# smallTransBrd.net
KiCad netlist of a schematic drawn in EAGLE
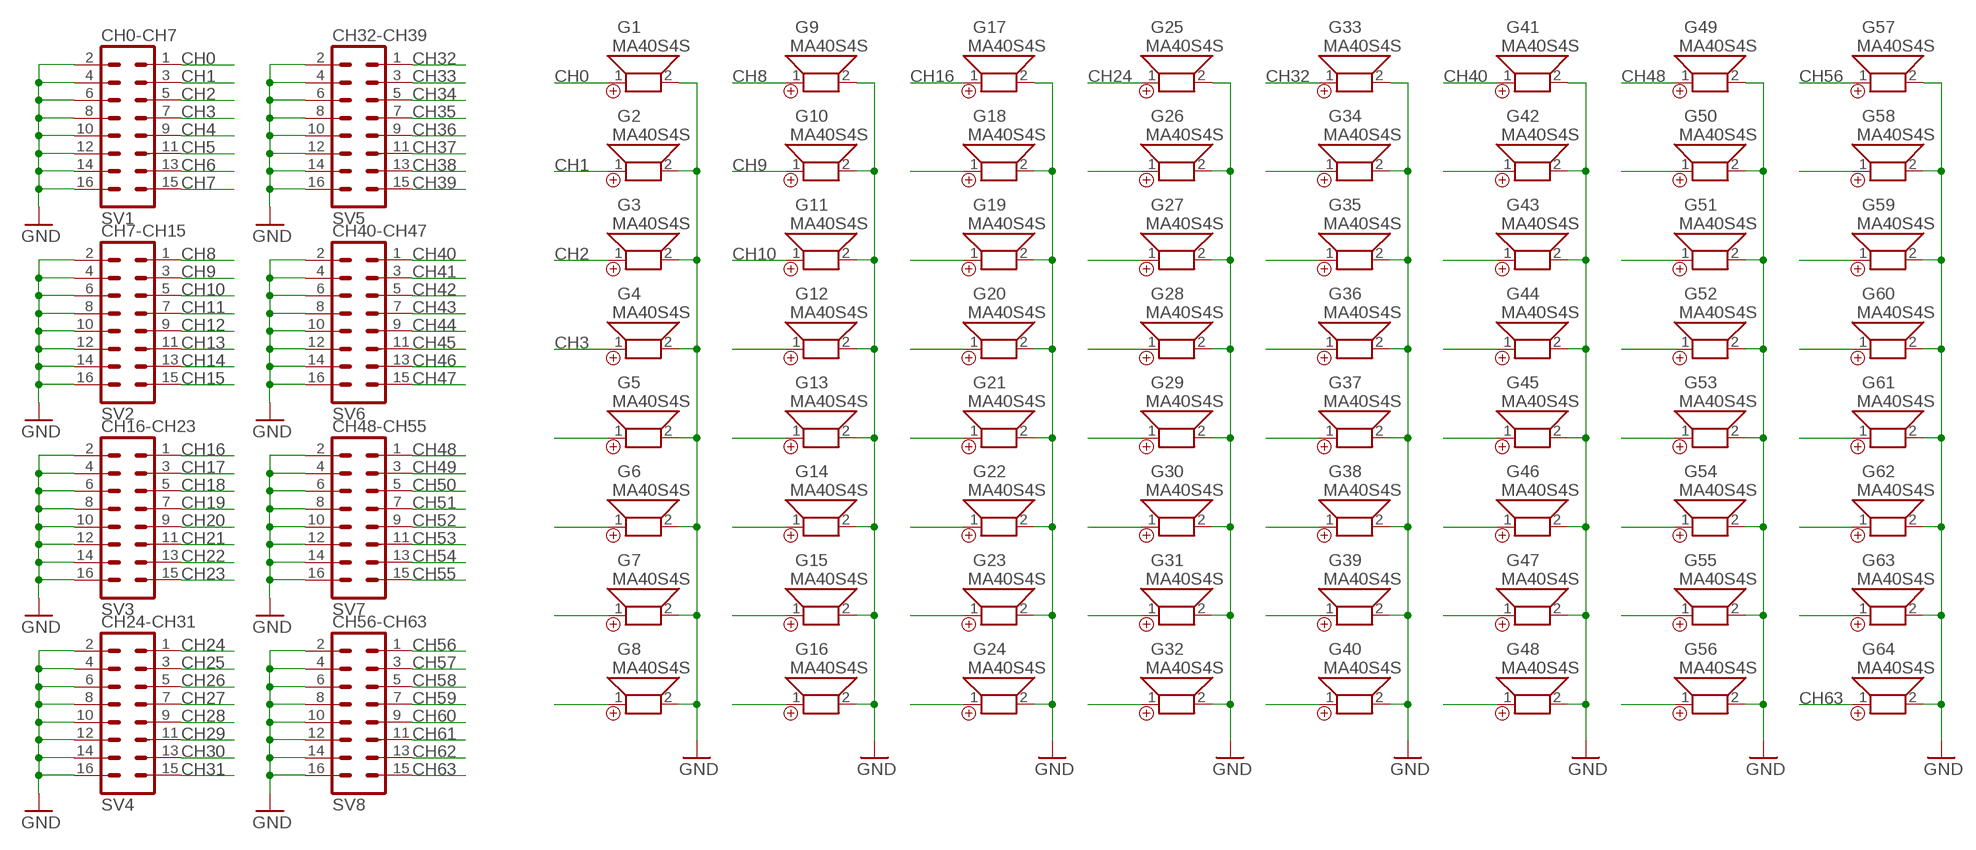
[diagram p0: schematic, sheet 1]

(export (version "E")
  (design (tool "Eeschema 10.0.6"))
  (components
    (comp (ref "G1")
      (value "MA40S4S")
      (footprint "eagle-import:MA40S4S")
      (libsource (lib "eagle-import") (part "MA40S4S"))
    )
    (comp (ref "G2")
      (value "MA40S4S")
      (footprint "eagle-import:MA40S4S")
      (libsource (lib "eagle-import") (part "MA40S4S"))
    )
    (comp (ref "G3")
      (value "MA40S4S")
      (footprint "eagle-import:MA40S4S")
      (libsource (lib "eagle-import") (part "MA40S4S"))
    )
    (comp (ref "G4")
      (value "MA40S4S")
      (footprint "eagle-import:MA40S4S")
      (libsource (lib "eagle-import") (part "MA40S4S"))
    )
    (comp (ref "G5")
      (value "MA40S4S")
      (footprint "eagle-import:MA40S4S")
      (libsource (lib "eagle-import") (part "MA40S4S"))
    )
    (comp (ref "G6")
      (value "MA40S4S")
      (footprint "eagle-import:MA40S4S")
      (libsource (lib "eagle-import") (part "MA40S4S"))
    )
    (comp (ref "G7")
      (value "MA40S4S")
      (footprint "eagle-import:MA40S4S")
      (libsource (lib "eagle-import") (part "MA40S4S"))
    )
    (comp (ref "G8")
      (value "MA40S4S")
      (footprint "eagle-import:MA40S4S")
      (libsource (lib "eagle-import") (part "MA40S4S"))
    )
    (comp (ref "G9")
      (value "MA40S4S")
      (footprint "eagle-import:MA40S4S")
      (libsource (lib "eagle-import") (part "MA40S4S"))
    )
    (comp (ref "G10")
      (value "MA40S4S")
      (footprint "eagle-import:MA40S4S")
      (libsource (lib "eagle-import") (part "MA40S4S"))
    )
    (comp (ref "G11")
      (value "MA40S4S")
      (footprint "eagle-import:MA40S4S")
      (libsource (lib "eagle-import") (part "MA40S4S"))
    )
    (comp (ref "G12")
      (value "MA40S4S")
      (footprint "eagle-import:MA40S4S")
      (libsource (lib "eagle-import") (part "MA40S4S"))
    )
    (comp (ref "G13")
      (value "MA40S4S")
      (footprint "eagle-import:MA40S4S")
      (libsource (lib "eagle-import") (part "MA40S4S"))
    )
    (comp (ref "G14")
      (value "MA40S4S")
      (footprint "eagle-import:MA40S4S")
      (libsource (lib "eagle-import") (part "MA40S4S"))
    )
    (comp (ref "G15")
      (value "MA40S4S")
      (footprint "eagle-import:MA40S4S")
      (libsource (lib "eagle-import") (part "MA40S4S"))
    )
    (comp (ref "G16")
      (value "MA40S4S")
      (footprint "eagle-import:MA40S4S")
      (libsource (lib "eagle-import") (part "MA40S4S"))
    )
    (comp (ref "G17")
      (value "MA40S4S")
      (footprint "eagle-import:MA40S4S")
      (libsource (lib "eagle-import") (part "MA40S4S"))
    )
    (comp (ref "G18")
      (value "MA40S4S")
      (footprint "eagle-import:MA40S4S")
      (libsource (lib "eagle-import") (part "MA40S4S"))
    )
    (comp (ref "G19")
      (value "MA40S4S")
      (footprint "eagle-import:MA40S4S")
      (libsource (lib "eagle-import") (part "MA40S4S"))
    )
    (comp (ref "G20")
      (value "MA40S4S")
      (footprint "eagle-import:MA40S4S")
      (libsource (lib "eagle-import") (part "MA40S4S"))
    )
    (comp (ref "G21")
      (value "MA40S4S")
      (footprint "eagle-import:MA40S4S")
      (libsource (lib "eagle-import") (part "MA40S4S"))
    )
    (comp (ref "G22")
      (value "MA40S4S")
      (footprint "eagle-import:MA40S4S")
      (libsource (lib "eagle-import") (part "MA40S4S"))
    )
    (comp (ref "G23")
      (value "MA40S4S")
      (footprint "eagle-import:MA40S4S")
      (libsource (lib "eagle-import") (part "MA40S4S"))
    )
    (comp (ref "G24")
      (value "MA40S4S")
      (footprint "eagle-import:MA40S4S")
      (libsource (lib "eagle-import") (part "MA40S4S"))
    )
    (comp (ref "G25")
      (value "MA40S4S")
      (footprint "eagle-import:MA40S4S")
      (libsource (lib "eagle-import") (part "MA40S4S"))
    )
    (comp (ref "G26")
      (value "MA40S4S")
      (footprint "eagle-import:MA40S4S")
      (libsource (lib "eagle-import") (part "MA40S4S"))
    )
    (comp (ref "G27")
      (value "MA40S4S")
      (footprint "eagle-import:MA40S4S")
      (libsource (lib "eagle-import") (part "MA40S4S"))
    )
    (comp (ref "G28")
      (value "MA40S4S")
      (footprint "eagle-import:MA40S4S")
      (libsource (lib "eagle-import") (part "MA40S4S"))
    )
    (comp (ref "G29")
      (value "MA40S4S")
      (footprint "eagle-import:MA40S4S")
      (libsource (lib "eagle-import") (part "MA40S4S"))
    )
    (comp (ref "G30")
      (value "MA40S4S")
      (footprint "eagle-import:MA40S4S")
      (libsource (lib "eagle-import") (part "MA40S4S"))
    )
    (comp (ref "G31")
      (value "MA40S4S")
      (footprint "eagle-import:MA40S4S")
      (libsource (lib "eagle-import") (part "MA40S4S"))
    )
    (comp (ref "G32")
      (value "MA40S4S")
      (footprint "eagle-import:MA40S4S")
      (libsource (lib "eagle-import") (part "MA40S4S"))
    )
    (comp (ref "G33")
      (value "MA40S4S")
      (footprint "eagle-import:MA40S4S")
      (libsource (lib "eagle-import") (part "MA40S4S"))
    )
    (comp (ref "G34")
      (value "MA40S4S")
      (footprint "eagle-import:MA40S4S")
      (libsource (lib "eagle-import") (part "MA40S4S"))
    )
    (comp (ref "G35")
      (value "MA40S4S")
      (footprint "eagle-import:MA40S4S")
      (libsource (lib "eagle-import") (part "MA40S4S"))
    )
    (comp (ref "G36")
      (value "MA40S4S")
      (footprint "eagle-import:MA40S4S")
      (libsource (lib "eagle-import") (part "MA40S4S"))
    )
    (comp (ref "G37")
      (value "MA40S4S")
      (footprint "eagle-import:MA40S4S")
      (libsource (lib "eagle-import") (part "MA40S4S"))
    )
    (comp (ref "G38")
      (value "MA40S4S")
      (footprint "eagle-import:MA40S4S")
      (libsource (lib "eagle-import") (part "MA40S4S"))
    )
    (comp (ref "G39")
      (value "MA40S4S")
      (footprint "eagle-import:MA40S4S")
      (libsource (lib "eagle-import") (part "MA40S4S"))
    )
    (comp (ref "G40")
      (value "MA40S4S")
      (footprint "eagle-import:MA40S4S")
      (libsource (lib "eagle-import") (part "MA40S4S"))
    )
    (comp (ref "G41")
      (value "MA40S4S")
      (footprint "eagle-import:MA40S4S")
      (libsource (lib "eagle-import") (part "MA40S4S"))
    )
    (comp (ref "G42")
      (value "MA40S4S")
      (footprint "eagle-import:MA40S4S")
      (libsource (lib "eagle-import") (part "MA40S4S"))
    )
    (comp (ref "G43")
      (value "MA40S4S")
      (footprint "eagle-import:MA40S4S")
      (libsource (lib "eagle-import") (part "MA40S4S"))
    )
    (comp (ref "G44")
      (value "MA40S4S")
      (footprint "eagle-import:MA40S4S")
      (libsource (lib "eagle-import") (part "MA40S4S"))
    )
    (comp (ref "G45")
      (value "MA40S4S")
      (footprint "eagle-import:MA40S4S")
      (libsource (lib "eagle-import") (part "MA40S4S"))
    )
    (comp (ref "G46")
      (value "MA40S4S")
      (footprint "eagle-import:MA40S4S")
      (libsource (lib "eagle-import") (part "MA40S4S"))
    )
    (comp (ref "G47")
      (value "MA40S4S")
      (footprint "eagle-import:MA40S4S")
      (libsource (lib "eagle-import") (part "MA40S4S"))
    )
    (comp (ref "G48")
      (value "MA40S4S")
      (footprint "eagle-import:MA40S4S")
      (libsource (lib "eagle-import") (part "MA40S4S"))
    )
    (comp (ref "G49")
      (value "MA40S4S")
      (footprint "eagle-import:MA40S4S")
      (libsource (lib "eagle-import") (part "MA40S4S"))
    )
    (comp (ref "G50")
      (value "MA40S4S")
      (footprint "eagle-import:MA40S4S")
      (libsource (lib "eagle-import") (part "MA40S4S"))
    )
    (comp (ref "G51")
      (value "MA40S4S")
      (footprint "eagle-import:MA40S4S")
      (libsource (lib "eagle-import") (part "MA40S4S"))
    )
    (comp (ref "G52")
      (value "MA40S4S")
      (footprint "eagle-import:MA40S4S")
      (libsource (lib "eagle-import") (part "MA40S4S"))
    )
    (comp (ref "G53")
      (value "MA40S4S")
      (footprint "eagle-import:MA40S4S")
      (libsource (lib "eagle-import") (part "MA40S4S"))
    )
    (comp (ref "G54")
      (value "MA40S4S")
      (footprint "eagle-import:MA40S4S")
      (libsource (lib "eagle-import") (part "MA40S4S"))
    )
    (comp (ref "G55")
      (value "MA40S4S")
      (footprint "eagle-import:MA40S4S")
      (libsource (lib "eagle-import") (part "MA40S4S"))
    )
    (comp (ref "G56")
      (value "MA40S4S")
      (footprint "eagle-import:MA40S4S")
      (libsource (lib "eagle-import") (part "MA40S4S"))
    )
    (comp (ref "G57")
      (value "MA40S4S")
      (footprint "eagle-import:MA40S4S")
      (libsource (lib "eagle-import") (part "MA40S4S"))
    )
    (comp (ref "G58")
      (value "MA40S4S")
      (footprint "eagle-import:MA40S4S")
      (libsource (lib "eagle-import") (part "MA40S4S"))
    )
    (comp (ref "G59")
      (value "MA40S4S")
      (footprint "eagle-import:MA40S4S")
      (libsource (lib "eagle-import") (part "MA40S4S"))
    )
    (comp (ref "G60")
      (value "MA40S4S")
      (footprint "eagle-import:MA40S4S")
      (libsource (lib "eagle-import") (part "MA40S4S"))
    )
    (comp (ref "G61")
      (value "MA40S4S")
      (footprint "eagle-import:MA40S4S")
      (libsource (lib "eagle-import") (part "MA40S4S"))
    )
    (comp (ref "G62")
      (value "MA40S4S")
      (footprint "eagle-import:MA40S4S")
      (libsource (lib "eagle-import") (part "MA40S4S"))
    )
    (comp (ref "G63")
      (value "MA40S4S")
      (footprint "eagle-import:MA40S4S")
      (libsource (lib "eagle-import") (part "MA40S4S"))
    )
    (comp (ref "G64")
      (value "MA40S4S")
      (footprint "eagle-import:MA40S4S")
      (libsource (lib "eagle-import") (part "MA40S4S"))
    )
    (comp (ref "SV1")
      (value "CH0-CH7")
      (footprint "eagle-import:ML16")
      (libsource (lib "eagle-import") (part "ML16"))
    )
    (comp (ref "SV2")
      (value "CH7-CH15")
      (footprint "eagle-import:ML16")
      (libsource (lib "eagle-import") (part "ML16"))
    )
    (comp (ref "SV3")
      (value "CH16-CH23")
      (footprint "eagle-import:ML16")
      (libsource (lib "eagle-import") (part "ML16"))
    )
    (comp (ref "SV4")
      (value "CH24-CH31")
      (footprint "eagle-import:ML16")
      (libsource (lib "eagle-import") (part "ML16"))
    )
    (comp (ref "SV5")
      (value "CH32-CH39")
      (footprint "eagle-import:ML16")
      (libsource (lib "eagle-import") (part "ML16"))
    )
    (comp (ref "SV6")
      (value "CH40-CH47")
      (footprint "eagle-import:ML16")
      (libsource (lib "eagle-import") (part "ML16"))
    )
    (comp (ref "SV7")
      (value "CH48-CH55")
      (footprint "eagle-import:ML16")
      (libsource (lib "eagle-import") (part "ML16"))
    )
    (comp (ref "SV8")
      (value "CH56-CH63")
      (footprint "eagle-import:ML16")
      (libsource (lib "eagle-import") (part "ML16"))
    )
  )
  (nets
    (net (code "1") (name "/CH0") (class "Default")
      (node (ref "G1") (pin "1") (pinfunction "1_1") (pintype "passive"))
      (node (ref "SV1") (pin "1") (pinfunction "1_1") (pintype "passive"))
    )
    (net (code "2") (name "/CH1") (class "Default")
      (node (ref "G2") (pin "1") (pinfunction "1_1") (pintype "passive"))
      (node (ref "SV1") (pin "3") (pinfunction "3_3") (pintype "passive"))
    )
    (net (code "3") (name "/CH2") (class "Default")
      (node (ref "G3") (pin "1") (pinfunction "1_1") (pintype "passive"))
      (node (ref "SV1") (pin "5") (pinfunction "5_5") (pintype "passive"))
    )
    (net (code "4") (name "/CH3") (class "Default")
      (node (ref "G4") (pin "1") (pinfunction "1_1") (pintype "passive"))
      (node (ref "SV1") (pin "7") (pinfunction "7_7") (pintype "passive"))
    )
    (net (code "5") (name "/CH4") (class "Default")
      (node (ref "G5") (pin "1") (pinfunction "1_1") (pintype "passive"))
      (node (ref "SV1") (pin "9") (pinfunction "9_9") (pintype "passive"))
    )
    (net (code "6") (name "/CH5") (class "Default")
      (node (ref "G6") (pin "1") (pinfunction "1_1") (pintype "passive"))
      (node (ref "SV1") (pin "11") (pinfunction "11_11") (pintype "passive"))
    )
    (net (code "7") (name "/CH6") (class "Default")
      (node (ref "G7") (pin "1") (pinfunction "1_1") (pintype "passive"))
      (node (ref "SV1") (pin "13") (pinfunction "13_13") (pintype "passive"))
    )
    (net (code "8") (name "/CH7") (class "Default")
      (node (ref "G8") (pin "1") (pinfunction "1_1") (pintype "passive"))
      (node (ref "SV1") (pin "15") (pinfunction "15_15") (pintype "passive"))
    )
    (net (code "9") (name "/CH8") (class "Default")
      (node (ref "G9") (pin "1") (pinfunction "1_1") (pintype "passive"))
      (node (ref "SV2") (pin "1") (pinfunction "1_1") (pintype "passive"))
    )
    (net (code "10") (name "/CH9") (class "Default")
      (node (ref "G10") (pin "1") (pinfunction "1_1") (pintype "passive"))
      (node (ref "SV2") (pin "3") (pinfunction "3_3") (pintype "passive"))
    )
    (net (code "11") (name "/CH10") (class "Default")
      (node (ref "G11") (pin "1") (pinfunction "1_1") (pintype "passive"))
      (node (ref "SV2") (pin "5") (pinfunction "5_5") (pintype "passive"))
    )
    (net (code "12") (name "/CH11") (class "Default")
      (node (ref "G12") (pin "1") (pinfunction "1_1") (pintype "passive"))
      (node (ref "SV2") (pin "7") (pinfunction "7_7") (pintype "passive"))
    )
    (net (code "13") (name "/CH12") (class "Default")
      (node (ref "G13") (pin "1") (pinfunction "1_1") (pintype "passive"))
      (node (ref "SV2") (pin "9") (pinfunction "9_9") (pintype "passive"))
    )
    (net (code "14") (name "/CH13") (class "Default")
      (node (ref "G14") (pin "1") (pinfunction "1_1") (pintype "passive"))
      (node (ref "SV2") (pin "11") (pinfunction "11_11") (pintype "passive"))
    )
    (net (code "15") (name "/CH14") (class "Default")
      (node (ref "G15") (pin "1") (pinfunction "1_1") (pintype "passive"))
      (node (ref "SV2") (pin "13") (pinfunction "13_13") (pintype "passive"))
    )
    (net (code "16") (name "/CH15") (class "Default")
      (node (ref "G16") (pin "1") (pinfunction "1_1") (pintype "passive"))
      (node (ref "SV2") (pin "15") (pinfunction "15_15") (pintype "passive"))
    )
    (net (code "17") (name "/CH16") (class "Default")
      (node (ref "G17") (pin "1") (pinfunction "1_1") (pintype "passive"))
      (node (ref "SV3") (pin "1") (pinfunction "1_1") (pintype "passive"))
    )
    (net (code "18") (name "/CH17") (class "Default")
      (node (ref "G18") (pin "1") (pinfunction "1_1") (pintype "passive"))
      (node (ref "SV3") (pin "3") (pinfunction "3_3") (pintype "passive"))
    )
    (net (code "19") (name "/CH18") (class "Default")
      (node (ref "G19") (pin "1") (pinfunction "1_1") (pintype "passive"))
      (node (ref "SV3") (pin "5") (pinfunction "5_5") (pintype "passive"))
    )
    (net (code "20") (name "/CH19") (class "Default")
      (node (ref "G20") (pin "1") (pinfunction "1_1") (pintype "passive"))
      (node (ref "SV3") (pin "7") (pinfunction "7_7") (pintype "passive"))
    )
    (net (code "21") (name "/CH20") (class "Default")
      (node (ref "G21") (pin "1") (pinfunction "1_1") (pintype "passive"))
      (node (ref "SV3") (pin "9") (pinfunction "9_9") (pintype "passive"))
    )
    (net (code "22") (name "/CH21") (class "Default")
      (node (ref "G22") (pin "1") (pinfunction "1_1") (pintype "passive"))
      (node (ref "SV3") (pin "11") (pinfunction "11_11") (pintype "passive"))
    )
    (net (code "23") (name "/CH22") (class "Default")
      (node (ref "G23") (pin "1") (pinfunction "1_1") (pintype "passive"))
      (node (ref "SV3") (pin "13") (pinfunction "13_13") (pintype "passive"))
    )
    (net (code "24") (name "/CH23") (class "Default")
      (node (ref "G24") (pin "1") (pinfunction "1_1") (pintype "passive"))
      (node (ref "SV3") (pin "15") (pinfunction "15_15") (pintype "passive"))
    )
    (net (code "25") (name "/CH24") (class "Default")
      (node (ref "G25") (pin "1") (pinfunction "1_1") (pintype "passive"))
      (node (ref "SV4") (pin "1") (pinfunction "1_1") (pintype "passive"))
    )
    (net (code "26") (name "/CH25") (class "Default")
      (node (ref "G26") (pin "1") (pinfunction "1_1") (pintype "passive"))
      (node (ref "SV4") (pin "3") (pinfunction "3_3") (pintype "passive"))
    )
    (net (code "27") (name "/CH26") (class "Default")
      (node (ref "G27") (pin "1") (pinfunction "1_1") (pintype "passive"))
      (node (ref "SV4") (pin "5") (pinfunction "5_5") (pintype "passive"))
    )
    (net (code "28") (name "/CH27") (class "Default")
      (node (ref "G28") (pin "1") (pinfunction "1_1") (pintype "passive"))
      (node (ref "SV4") (pin "7") (pinfunction "7_7") (pintype "passive"))
    )
    (net (code "29") (name "/CH28") (class "Default")
      (node (ref "G29") (pin "1") (pinfunction "1_1") (pintype "passive"))
      (node (ref "SV4") (pin "9") (pinfunction "9_9") (pintype "passive"))
    )
    (net (code "30") (name "/CH29") (class "Default")
      (node (ref "G30") (pin "1") (pinfunction "1_1") (pintype "passive"))
      (node (ref "SV4") (pin "11") (pinfunction "11_11") (pintype "passive"))
    )
    (net (code "31") (name "/CH30") (class "Default")
      (node (ref "G31") (pin "1") (pinfunction "1_1") (pintype "passive"))
      (node (ref "SV4") (pin "13") (pinfunction "13_13") (pintype "passive"))
    )
    (net (code "32") (name "/CH31") (class "Default")
      (node (ref "G32") (pin "1") (pinfunction "1_1") (pintype "passive"))
      (node (ref "SV4") (pin "15") (pinfunction "15_15") (pintype "passive"))
    )
    (net (code "33") (name "/CH32") (class "Default")
      (node (ref "G33") (pin "1") (pinfunction "1_1") (pintype "passive"))
      (node (ref "SV5") (pin "1") (pinfunction "1_1") (pintype "passive"))
    )
    (net (code "34") (name "/CH33") (class "Default")
      (node (ref "G34") (pin "1") (pinfunction "1_1") (pintype "passive"))
      (node (ref "SV5") (pin "3") (pinfunction "3_3") (pintype "passive"))
    )
    (net (code "35") (name "/CH34") (class "Default")
      (node (ref "G35") (pin "1") (pinfunction "1_1") (pintype "passive"))
      (node (ref "SV5") (pin "5") (pinfunction "5_5") (pintype "passive"))
    )
    (net (code "36") (name "/CH35") (class "Default")
      (node (ref "G36") (pin "1") (pinfunction "1_1") (pintype "passive"))
      (node (ref "SV5") (pin "7") (pinfunction "7_7") (pintype "passive"))
    )
    (net (code "37") (name "/CH36") (class "Default")
      (node (ref "G37") (pin "1") (pinfunction "1_1") (pintype "passive"))
      (node (ref "SV5") (pin "9") (pinfunction "9_9") (pintype "passive"))
    )
    (net (code "38") (name "/CH37") (class "Default")
      (node (ref "G38") (pin "1") (pinfunction "1_1") (pintype "passive"))
      (node (ref "SV5") (pin "11") (pinfunction "11_11") (pintype "passive"))
    )
    (net (code "39") (name "/CH38") (class "Default")
      (node (ref "G39") (pin "1") (pinfunction "1_1") (pintype "passive"))
      (node (ref "SV5") (pin "13") (pinfunction "13_13") (pintype "passive"))
    )
    (net (code "40") (name "/CH39") (class "Default")
      (node (ref "G40") (pin "1") (pinfunction "1_1") (pintype "passive"))
      (node (ref "SV5") (pin "15") (pinfunction "15_15") (pintype "passive"))
    )
    (net (code "41") (name "/CH40") (class "Default")
      (node (ref "G41") (pin "1") (pinfunction "1_1") (pintype "passive"))
      (node (ref "SV6") (pin "1") (pinfunction "1_1") (pintype "passive"))
    )
    (net (code "42") (name "/CH41") (class "Default")
      (node (ref "G42") (pin "1") (pinfunction "1_1") (pintype "passive"))
      (node (ref "SV6") (pin "3") (pinfunction "3_3") (pintype "passive"))
    )
    (net (code "43") (name "/CH42") (class "Default")
      (node (ref "G43") (pin "1") (pinfunction "1_1") (pintype "passive"))
      (node (ref "SV6") (pin "5") (pinfunction "5_5") (pintype "passive"))
    )
    (net (code "44") (name "/CH43") (class "Default")
      (node (ref "G44") (pin "1") (pinfunction "1_1") (pintype "passive"))
      (node (ref "SV6") (pin "7") (pinfunction "7_7") (pintype "passive"))
    )
    (net (code "45") (name "/CH44") (class "Default")
      (node (ref "G45") (pin "1") (pinfunction "1_1") (pintype "passive"))
      (node (ref "SV6") (pin "9") (pinfunction "9_9") (pintype "passive"))
    )
    (net (code "46") (name "/CH45") (class "Default")
      (node (ref "G46") (pin "1") (pinfunction "1_1") (pintype "passive"))
      (node (ref "SV6") (pin "11") (pinfunction "11_11") (pintype "passive"))
    )
    (net (code "47") (name "/CH46") (class "Default")
      (node (ref "G47") (pin "1") (pinfunction "1_1") (pintype "passive"))
      (node (ref "SV6") (pin "13") (pinfunction "13_13") (pintype "passive"))
    )
    (net (code "48") (name "/CH47") (class "Default")
      (node (ref "G48") (pin "1") (pinfunction "1_1") (pintype "passive"))
      (node (ref "SV6") (pin "15") (pinfunction "15_15") (pintype "passive"))
    )
    (net (code "49") (name "/CH48") (class "Default")
      (node (ref "G49") (pin "1") (pinfunction "1_1") (pintype "passive"))
      (node (ref "SV7") (pin "1") (pinfunction "1_1") (pintype "passive"))
    )
    (net (code "50") (name "/CH49") (class "Default")
      (node (ref "G50") (pin "1") (pinfunction "1_1") (pintype "passive"))
      (node (ref "SV7") (pin "3") (pinfunction "3_3") (pintype "passive"))
    )
    (net (code "51") (name "/CH50") (class "Default")
      (node (ref "G51") (pin "1") (pinfunction "1_1") (pintype "passive"))
      (node (ref "SV7") (pin "5") (pinfunction "5_5") (pintype "passive"))
    )
    (net (code "52") (name "/CH51") (class "Default")
      (node (ref "G52") (pin "1") (pinfunction "1_1") (pintype "passive"))
      (node (ref "SV7") (pin "7") (pinfunction "7_7") (pintype "passive"))
    )
    (net (code "53") (name "/CH52") (class "Default")
      (node (ref "G53") (pin "1") (pinfunction "1_1") (pintype "passive"))
      (node (ref "SV7") (pin "9") (pinfunction "9_9") (pintype "passive"))
    )
    (net (code "54") (name "/CH53") (class "Default")
      (node (ref "G54") (pin "1") (pinfunction "1_1") (pintype "passive"))
      (node (ref "SV7") (pin "11") (pinfunction "11_11") (pintype "passive"))
    )
    (net (code "55") (name "/CH54") (class "Default")
      (node (ref "G55") (pin "1") (pinfunction "1_1") (pintype "passive"))
      (node (ref "SV7") (pin "13") (pinfunction "13_13") (pintype "passive"))
    )
    (net (code "56") (name "/CH55") (class "Default")
      (node (ref "G56") (pin "1") (pinfunction "1_1") (pintype "passive"))
      (node (ref "SV7") (pin "15") (pinfunction "15_15") (pintype "passive"))
    )
    (net (code "57") (name "/CH56") (class "Default")
      (node (ref "G57") (pin "1") (pinfunction "1_1") (pintype "passive"))
      (node (ref "SV8") (pin "1") (pinfunction "1_1") (pintype "passive"))
    )
    (net (code "58") (name "/CH57") (class "Default")
      (node (ref "G58") (pin "1") (pinfunction "1_1") (pintype "passive"))
      (node (ref "SV8") (pin "3") (pinfunction "3_3") (pintype "passive"))
    )
    (net (code "59") (name "/CH58") (class "Default")
      (node (ref "G59") (pin "1") (pinfunction "1_1") (pintype "passive"))
      (node (ref "SV8") (pin "5") (pinfunction "5_5") (pintype "passive"))
    )
    (net (code "60") (name "/CH59") (class "Default")
      (node (ref "G60") (pin "1") (pinfunction "1_1") (pintype "passive"))
      (node (ref "SV8") (pin "7") (pinfunction "7_7") (pintype "passive"))
    )
    (net (code "61") (name "/CH60") (class "Default")
      (node (ref "G61") (pin "1") (pinfunction "1_1") (pintype "passive"))
      (node (ref "SV8") (pin "9") (pinfunction "9_9") (pintype "passive"))
    )
    (net (code "62") (name "/CH61") (class "Default")
      (node (ref "G62") (pin "1") (pinfunction "1_1") (pintype "passive"))
      (node (ref "SV8") (pin "11") (pinfunction "11_11") (pintype "passive"))
    )
    (net (code "63") (name "/CH62") (class "Default")
      (node (ref "G63") (pin "1") (pinfunction "1_1") (pintype "passive"))
      (node (ref "SV8") (pin "13") (pinfunction "13_13") (pintype "passive"))
    )
    (net (code "64") (name "/CH63") (class "Default")
      (node (ref "G64") (pin "1") (pinfunction "1_1") (pintype "passive"))
      (node (ref "SV8") (pin "15") (pinfunction "15_15") (pintype "passive"))
    )
    (net (code "65") (name "GND") (class "Default")
      (node (ref "G1") (pin "2") (pinfunction "2_2") (pintype "passive"))
      (node (ref "G10") (pin "2") (pinfunction "2_2") (pintype "passive"))
      (node (ref "G11") (pin "2") (pinfunction "2_2") (pintype "passive"))
      (node (ref "G12") (pin "2") (pinfunction "2_2") (pintype "passive"))
      (node (ref "G13") (pin "2") (pinfunction "2_2") (pintype "passive"))
      (node (ref "G14") (pin "2") (pinfunction "2_2") (pintype "passive"))
      (node (ref "G15") (pin "2") (pinfunction "2_2") (pintype "passive"))
      (node (ref "G16") (pin "2") (pinfunction "2_2") (pintype "passive"))
      (node (ref "G17") (pin "2") (pinfunction "2_2") (pintype "passive"))
      (node (ref "G18") (pin "2") (pinfunction "2_2") (pintype "passive"))
      (node (ref "G19") (pin "2") (pinfunction "2_2") (pintype "passive"))
      (node (ref "G2") (pin "2") (pinfunction "2_2") (pintype "passive"))
      (node (ref "G20") (pin "2") (pinfunction "2_2") (pintype "passive"))
      (node (ref "G21") (pin "2") (pinfunction "2_2") (pintype "passive"))
      (node (ref "G22") (pin "2") (pinfunction "2_2") (pintype "passive"))
      (node (ref "G23") (pin "2") (pinfunction "2_2") (pintype "passive"))
      (node (ref "G24") (pin "2") (pinfunction "2_2") (pintype "passive"))
      (node (ref "G25") (pin "2") (pinfunction "2_2") (pintype "passive"))
      (node (ref "G26") (pin "2") (pinfunction "2_2") (pintype "passive"))
      (node (ref "G27") (pin "2") (pinfunction "2_2") (pintype "passive"))
      (node (ref "G28") (pin "2") (pinfunction "2_2") (pintype "passive"))
      (node (ref "G29") (pin "2") (pinfunction "2_2") (pintype "passive"))
      (node (ref "G3") (pin "2") (pinfunction "2_2") (pintype "passive"))
      (node (ref "G30") (pin "2") (pinfunction "2_2") (pintype "passive"))
      (node (ref "G31") (pin "2") (pinfunction "2_2") (pintype "passive"))
      (node (ref "G32") (pin "2") (pinfunction "2_2") (pintype "passive"))
      (node (ref "G33") (pin "2") (pinfunction "2_2") (pintype "passive"))
      (node (ref "G34") (pin "2") (pinfunction "2_2") (pintype "passive"))
      (node (ref "G35") (pin "2") (pinfunction "2_2") (pintype "passive"))
      (node (ref "G36") (pin "2") (pinfunction "2_2") (pintype "passive"))
      (node (ref "G37") (pin "2") (pinfunction "2_2") (pintype "passive"))
      (node (ref "G38") (pin "2") (pinfunction "2_2") (pintype "passive"))
      (node (ref "G39") (pin "2") (pinfunction "2_2") (pintype "passive"))
      (node (ref "G4") (pin "2") (pinfunction "2_2") (pintype "passive"))
      (node (ref "G40") (pin "2") (pinfunction "2_2") (pintype "passive"))
      (node (ref "G41") (pin "2") (pinfunction "2_2") (pintype "passive"))
      (node (ref "G42") (pin "2") (pinfunction "2_2") (pintype "passive"))
      (node (ref "G43") (pin "2") (pinfunction "2_2") (pintype "passive"))
      (node (ref "G44") (pin "2") (pinfunction "2_2") (pintype "passive"))
      (node (ref "G45") (pin "2") (pinfunction "2_2") (pintype "passive"))
      (node (ref "G46") (pin "2") (pinfunction "2_2") (pintype "passive"))
      (node (ref "G47") (pin "2") (pinfunction "2_2") (pintype "passive"))
      (node (ref "G48") (pin "2") (pinfunction "2_2") (pintype "passive"))
      (node (ref "G49") (pin "2") (pinfunction "2_2") (pintype "passive"))
      (node (ref "G5") (pin "2") (pinfunction "2_2") (pintype "passive"))
      (node (ref "G50") (pin "2") (pinfunction "2_2") (pintype "passive"))
      (node (ref "G51") (pin "2") (pinfunction "2_2") (pintype "passive"))
      (node (ref "G52") (pin "2") (pinfunction "2_2") (pintype "passive"))
      (node (ref "G53") (pin "2") (pinfunction "2_2") (pintype "passive"))
      (node (ref "G54") (pin "2") (pinfunction "2_2") (pintype "passive"))
      (node (ref "G55") (pin "2") (pinfunction "2_2") (pintype "passive"))
      (node (ref "G56") (pin "2") (pinfunction "2_2") (pintype "passive"))
      (node (ref "G57") (pin "2") (pinfunction "2_2") (pintype "passive"))
      (node (ref "G58") (pin "2") (pinfunction "2_2") (pintype "passive"))
      (node (ref "G59") (pin "2") (pinfunction "2_2") (pintype "passive"))
      (node (ref "G6") (pin "2") (pinfunction "2_2") (pintype "passive"))
      (node (ref "G60") (pin "2") (pinfunction "2_2") (pintype "passive"))
      (node (ref "G61") (pin "2") (pinfunction "2_2") (pintype "passive"))
      (node (ref "G62") (pin "2") (pinfunction "2_2") (pintype "passive"))
      (node (ref "G63") (pin "2") (pinfunction "2_2") (pintype "passive"))
      (node (ref "G64") (pin "2") (pinfunction "2_2") (pintype "passive"))
      (node (ref "G7") (pin "2") (pinfunction "2_2") (pintype "passive"))
      (node (ref "G8") (pin "2") (pinfunction "2_2") (pintype "passive"))
      (node (ref "G9") (pin "2") (pinfunction "2_2") (pintype "passive"))
      (node (ref "SV1") (pin "10") (pinfunction "10_10") (pintype "passive"))
      (node (ref "SV1") (pin "12") (pinfunction "12_12") (pintype "passive"))
      (node (ref "SV1") (pin "14") (pinfunction "14_14") (pintype "passive"))
      (node (ref "SV1") (pin "16") (pinfunction "16_16") (pintype "passive"))
      (node (ref "SV1") (pin "2") (pinfunction "2_2") (pintype "passive"))
      (node (ref "SV1") (pin "4") (pinfunction "4_4") (pintype "passive"))
      (node (ref "SV1") (pin "6") (pinfunction "6_6") (pintype "passive"))
      (node (ref "SV1") (pin "8") (pinfunction "8_8") (pintype "passive"))
      (node (ref "SV2") (pin "10") (pinfunction "10_10") (pintype "passive"))
      (node (ref "SV2") (pin "12") (pinfunction "12_12") (pintype "passive"))
      (node (ref "SV2") (pin "14") (pinfunction "14_14") (pintype "passive"))
      (node (ref "SV2") (pin "16") (pinfunction "16_16") (pintype "passive"))
      (node (ref "SV2") (pin "2") (pinfunction "2_2") (pintype "passive"))
      (node (ref "SV2") (pin "4") (pinfunction "4_4") (pintype "passive"))
      (node (ref "SV2") (pin "6") (pinfunction "6_6") (pintype "passive"))
      (node (ref "SV2") (pin "8") (pinfunction "8_8") (pintype "passive"))
      (node (ref "SV3") (pin "10") (pinfunction "10_10") (pintype "passive"))
      (node (ref "SV3") (pin "12") (pinfunction "12_12") (pintype "passive"))
      (node (ref "SV3") (pin "14") (pinfunction "14_14") (pintype "passive"))
      (node (ref "SV3") (pin "16") (pinfunction "16_16") (pintype "passive"))
      (node (ref "SV3") (pin "2") (pinfunction "2_2") (pintype "passive"))
      (node (ref "SV3") (pin "4") (pinfunction "4_4") (pintype "passive"))
      (node (ref "SV3") (pin "6") (pinfunction "6_6") (pintype "passive"))
      (node (ref "SV3") (pin "8") (pinfunction "8_8") (pintype "passive"))
      (node (ref "SV4") (pin "10") (pinfunction "10_10") (pintype "passive"))
      (node (ref "SV4") (pin "12") (pinfunction "12_12") (pintype "passive"))
      (node (ref "SV4") (pin "14") (pinfunction "14_14") (pintype "passive"))
      (node (ref "SV4") (pin "16") (pinfunction "16_16") (pintype "passive"))
      (node (ref "SV4") (pin "2") (pinfunction "2_2") (pintype "passive"))
      (node (ref "SV4") (pin "4") (pinfunction "4_4") (pintype "passive"))
      (node (ref "SV4") (pin "6") (pinfunction "6_6") (pintype "passive"))
      (node (ref "SV4") (pin "8") (pinfunction "8_8") (pintype "passive"))
      (node (ref "SV5") (pin "10") (pinfunction "10_10") (pintype "passive"))
      (node (ref "SV5") (pin "12") (pinfunction "12_12") (pintype "passive"))
      (node (ref "SV5") (pin "14") (pinfunction "14_14") (pintype "passive"))
      (node (ref "SV5") (pin "16") (pinfunction "16_16") (pintype "passive"))
      (node (ref "SV5") (pin "2") (pinfunction "2_2") (pintype "passive"))
      (node (ref "SV5") (pin "4") (pinfunction "4_4") (pintype "passive"))
      (node (ref "SV5") (pin "6") (pinfunction "6_6") (pintype "passive"))
      (node (ref "SV5") (pin "8") (pinfunction "8_8") (pintype "passive"))
      (node (ref "SV6") (pin "10") (pinfunction "10_10") (pintype "passive"))
      (node (ref "SV6") (pin "12") (pinfunction "12_12") (pintype "passive"))
      (node (ref "SV6") (pin "14") (pinfunction "14_14") (pintype "passive"))
      (node (ref "SV6") (pin "16") (pinfunction "16_16") (pintype "passive"))
      (node (ref "SV6") (pin "2") (pinfunction "2_2") (pintype "passive"))
      (node (ref "SV6") (pin "4") (pinfunction "4_4") (pintype "passive"))
      (node (ref "SV6") (pin "6") (pinfunction "6_6") (pintype "passive"))
      (node (ref "SV6") (pin "8") (pinfunction "8_8") (pintype "passive"))
      (node (ref "SV7") (pin "10") (pinfunction "10_10") (pintype "passive"))
      (node (ref "SV7") (pin "12") (pinfunction "12_12") (pintype "passive"))
      (node (ref "SV7") (pin "14") (pinfunction "14_14") (pintype "passive"))
      (node (ref "SV7") (pin "16") (pinfunction "16_16") (pintype "passive"))
      (node (ref "SV7") (pin "2") (pinfunction "2_2") (pintype "passive"))
      (node (ref "SV7") (pin "4") (pinfunction "4_4") (pintype "passive"))
      (node (ref "SV7") (pin "6") (pinfunction "6_6") (pintype "passive"))
      (node (ref "SV7") (pin "8") (pinfunction "8_8") (pintype "passive"))
      (node (ref "SV8") (pin "10") (pinfunction "10_10") (pintype "passive"))
      (node (ref "SV8") (pin "12") (pinfunction "12_12") (pintype "passive"))
      (node (ref "SV8") (pin "14") (pinfunction "14_14") (pintype "passive"))
      (node (ref "SV8") (pin "16") (pinfunction "16_16") (pintype "passive"))
      (node (ref "SV8") (pin "2") (pinfunction "2_2") (pintype "passive"))
      (node (ref "SV8") (pin "4") (pinfunction "4_4") (pintype "passive"))
      (node (ref "SV8") (pin "6") (pinfunction "6_6") (pintype "passive"))
      (node (ref "SV8") (pin "8") (pinfunction "8_8") (pintype "passive"))
    )
  )
)
